# SCH__Atlas_2026-06-22.net
KiCad netlist of a schematic drawn in EasyEDA
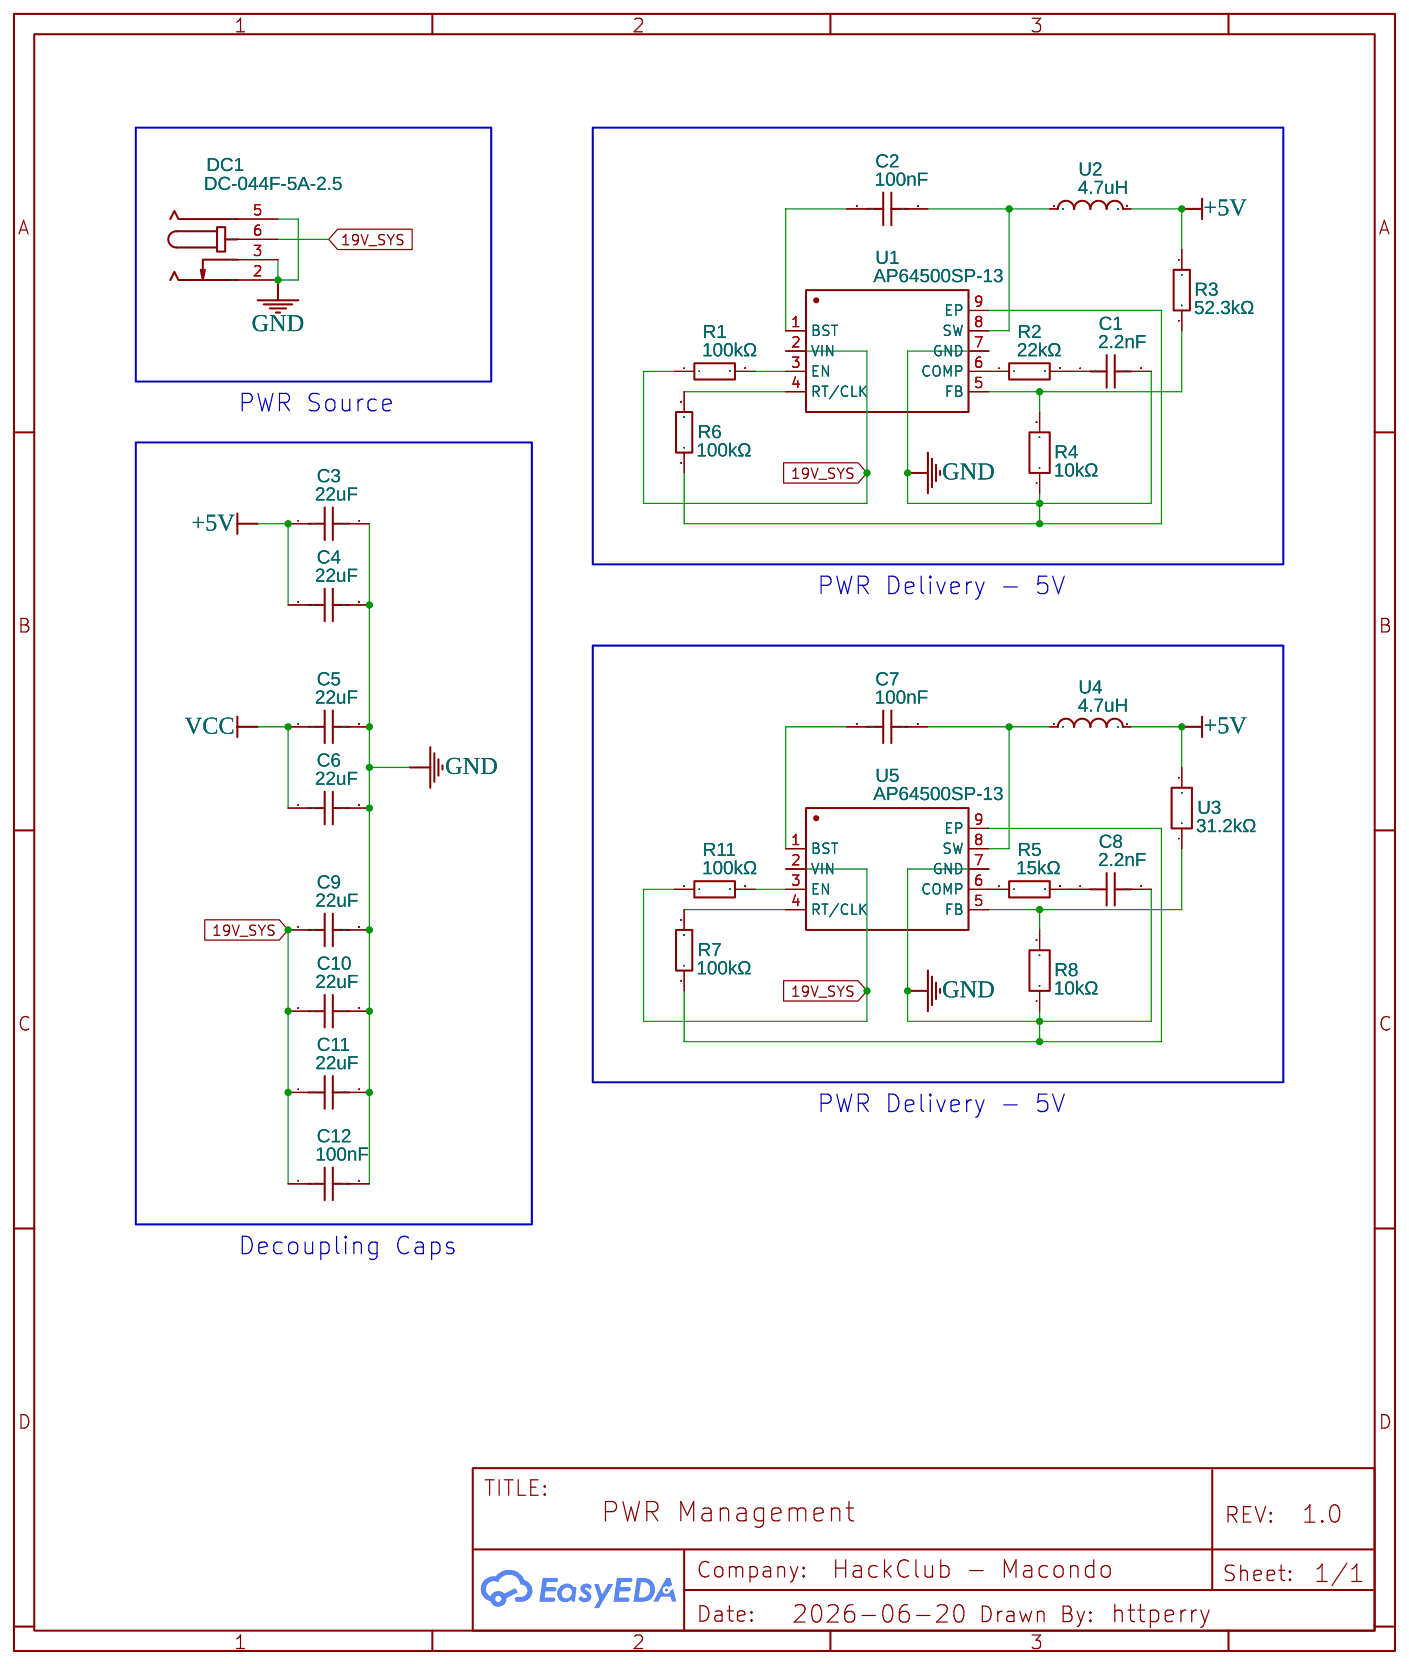
[diagram p0: PWR_Management]
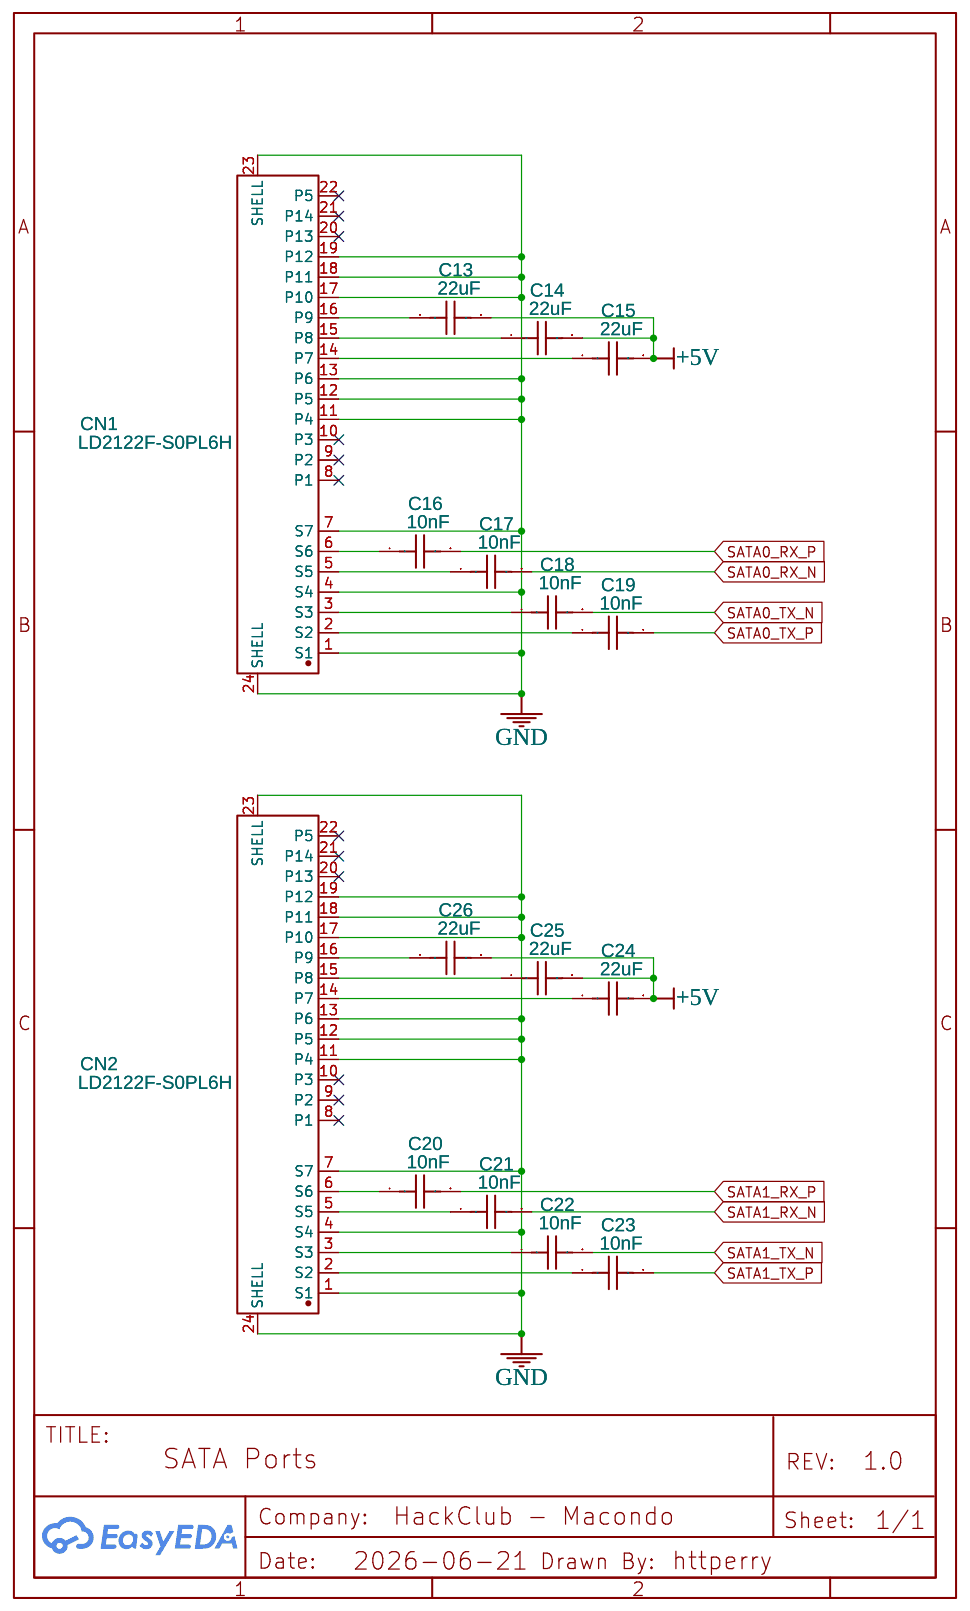
[diagram p1: SATA_Ports]
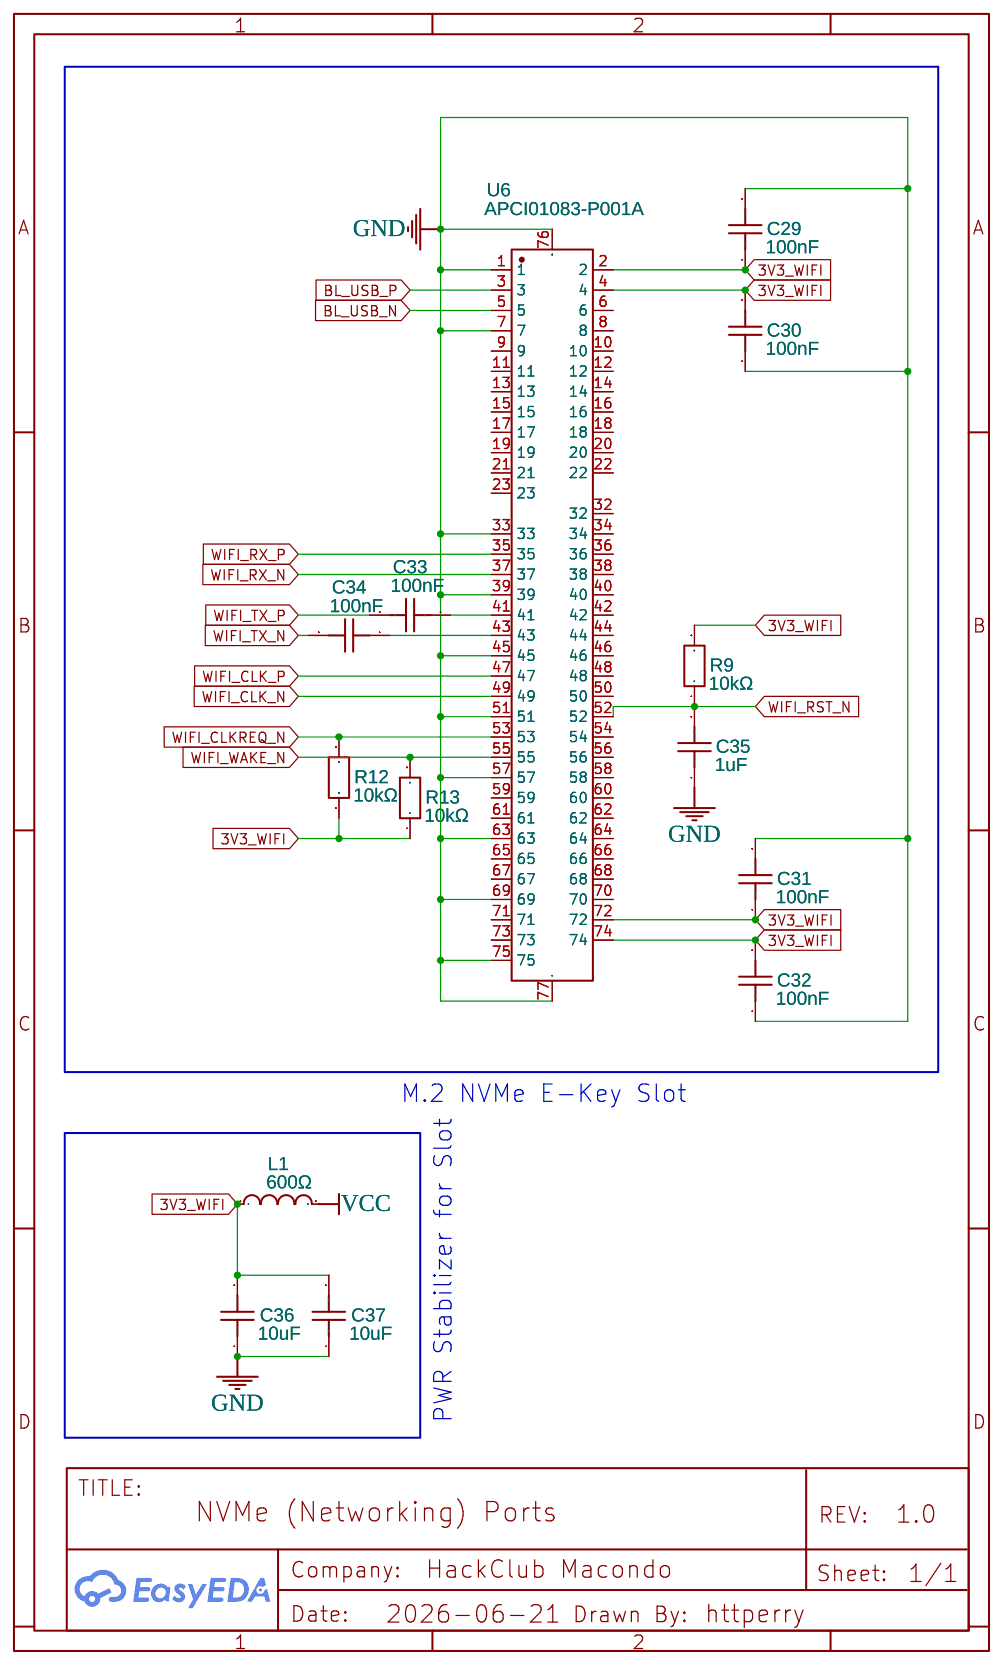
[diagram p2: NVMe_(Networking)_Ports]
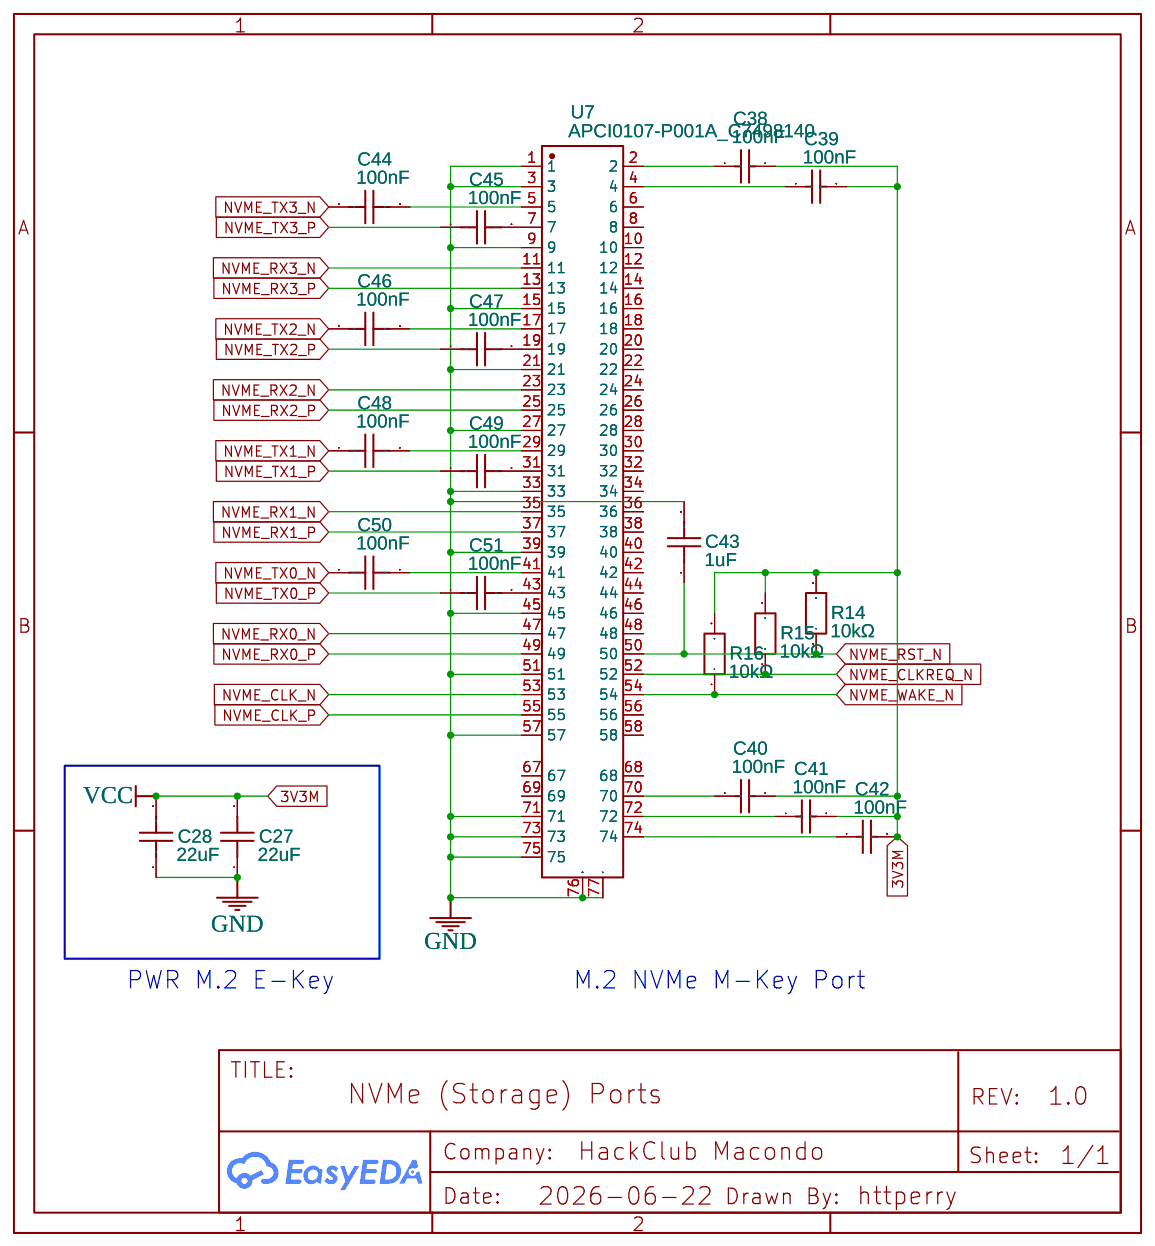
[diagram p3: NVMe_(Storage)_Ports]

(export (version "E")
  (design (tool "Eeschema 10.0.6"))
  (components
    (comp (ref "C1")
      (value "2.2nF")
      (fields
        (field (name "Manufacturer Part") "FCC0603B222K500CT")
        (field (name "Manufacturer") "FOJAN(富捷)")
      )
      (libsource (lib "") (part "FCC0603B222K500CT"))
    )
    (comp (ref "C2")
      (value "100nF")
      (fields
        (field (name "Manufacturer Part") "GRM188R71H104KA93D")
        (field (name "Manufacturer") "muRata(村田)")
      )
      (libsource (lib "") (part "GRM188R71H104KA93D"))
    )
    (comp (ref "C3")
      (value "22uF")
      (fields
        (field (name "Manufacturer Part") "HGC0603R5226M160NTHJ")
        (field (name "Manufacturer") "Chinocera(华瓷)")
      )
      (libsource (lib "") (part "HGC0603R5226M160NTHJ"))
    )
    (comp (ref "C4")
      (value "22uF")
      (fields
        (field (name "Manufacturer Part") "HGC0603R5226M160NTHJ")
        (field (name "Manufacturer") "Chinocera(华瓷)")
      )
      (libsource (lib "") (part "HGC0603R5226M160NTHJ"))
    )
    (comp (ref "C5")
      (value "22uF")
      (fields
        (field (name "Manufacturer Part") "HGC0603R5226M160NTHJ")
        (field (name "Manufacturer") "Chinocera(华瓷)")
      )
      (libsource (lib "") (part "HGC0603R5226M160NTHJ"))
    )
    (comp (ref "C6")
      (value "22uF")
      (fields
        (field (name "Manufacturer Part") "HGC0603R5226M160NTHJ")
        (field (name "Manufacturer") "Chinocera(华瓷)")
      )
      (libsource (lib "") (part "HGC0603R5226M160NTHJ"))
    )
    (comp (ref "C7")
      (value "100nF")
      (fields
        (field (name "Manufacturer Part") "GRM188R71H104KA93D")
        (field (name "Manufacturer") "muRata(村田)")
      )
      (libsource (lib "") (part "GRM188R71H104KA93D"))
    )
    (comp (ref "C8")
      (value "2.2nF")
      (fields
        (field (name "Manufacturer Part") "FCC0603B222K500CT")
        (field (name "Manufacturer") "FOJAN(富捷)")
      )
      (libsource (lib "") (part "FCC0603B222K500CT"))
    )
    (comp (ref "C9")
      (value "22uF")
      (fields
        (field (name "Manufacturer Part") "KCM55QR71H226KH13K")
        (field (name "Manufacturer") "muRata(村田)")
      )
      (libsource (lib "") (part "KCM55QR71H226KH13K"))
    )
    (comp (ref "C10")
      (value "22uF")
      (fields
        (field (name "Manufacturer Part") "KCM55QR71H226KH13K")
        (field (name "Manufacturer") "muRata(村田)")
      )
      (libsource (lib "") (part "KCM55QR71H226KH13K"))
    )
    (comp (ref "C11")
      (value "22uF")
      (fields
        (field (name "Manufacturer Part") "KCM55QR71H226KH13K")
        (field (name "Manufacturer") "muRata(村田)")
      )
      (libsource (lib "") (part "KCM55QR71H226KH13K"))
    )
    (comp (ref "C12")
      (value "100nF")
      (fields
        (field (name "Manufacturer Part") "GRM188R71H104KA93D")
        (field (name "Manufacturer") "muRata(村田)")
      )
      (libsource (lib "") (part "GRM188R71H104KA93D"))
    )
    (comp (ref "DC1")
      (value "DC-044F-5A-2.5")
      (fields (field (name "Manufacturer") "XKB Connection(中国星坤)"))
      (libsource (lib "") (part "DC-044F-5A-2.5"))
    )
    (comp (ref "R1")
      (value "100kΩ")
      (fields (field (name "Manufacturer Part") "RS-03K1003FT") (field (name "Manufacturer") "FH(风华)"))
      (libsource (lib "") (part "RS-03K1003FT_C115320"))
    )
    (comp (ref "R2")
      (value "22kΩ")
      (fields (field (name "Manufacturer Part") "RS-03K2202FT") (field (name "Manufacturer") "FH(风华)"))
      (libsource (lib "") (part "RS-03K2202FT"))
    )
    (comp (ref "R3")
      (value "52.3kΩ")
      (fields (field (name "Manufacturer Part") "RS-03K5232FT") (field (name "Manufacturer") "FH(风华)"))
      (libsource (lib "") (part "RS-03K5232FT"))
    )
    (comp (ref "R4")
      (value "10kΩ")
      (fields (field (name "Manufacturer Part") "AR03BTS1002") (field (name "Manufacturer") "Viking(光颉)"))
      (libsource (lib "") (part "AR03BTS1002"))
    )
    (comp (ref "R5")
      (value "15kΩ")
      (fields (field (name "Manufacturer Part") "CR0603FA1502G") (field (name "Manufacturer") "LIZ(丽智电子)"))
      (libsource (lib "") (part "CR0603FA1502G"))
    )
    (comp (ref "R6")
      (value "100kΩ")
      (fields (field (name "Manufacturer Part") "RS-03K1003FT") (field (name "Manufacturer") "FH(风华)"))
      (libsource (lib "") (part "RS-03K1003FT_C115320_1"))
    )
    (comp (ref "R7")
      (value "100kΩ")
      (fields (field (name "Manufacturer Part") "RS-03K1003FT") (field (name "Manufacturer") "FH(风华)"))
      (libsource (lib "") (part "RS-03K1003FT_C115320_1"))
    )
    (comp (ref "R8")
      (value "10kΩ")
      (fields (field (name "Manufacturer Part") "AR03BTS1002") (field (name "Manufacturer") "Viking(光颉)"))
      (libsource (lib "") (part "AR03BTS1002"))
    )
    (comp (ref "R11")
      (value "100kΩ")
      (fields (field (name "Manufacturer Part") "RS-03K1003FT") (field (name "Manufacturer") "FH(风华)"))
      (libsource (lib "") (part "RS-03K1003FT_C115320"))
    )
    (comp (ref "U1")
      (value "AP64500SP-13")
      (fields (field (name "Manufacturer") "DIODES(美台)"))
      (libsource (lib "") (part "AP64500SP-13"))
    )
    (comp (ref "U2")
      (value "4.7uH")
      (fields (field (name "Manufacturer Part") "APH0630T4R7M") (field (name "Manufacturer") "APV(爱普微)"))
      (libsource (lib "") (part "APH0630T4R7M"))
    )
    (comp (ref "U3")
      (value "31.2kΩ")
      (fields (field (name "Manufacturer Part") "RT0603DRE0731K2L") (field (name "Manufacturer") "YAGEO(国巨)"))
      (libsource (lib "") (part "RT0603DRE0731K2L"))
    )
    (comp (ref "U4")
      (value "4.7uH")
      (fields (field (name "Manufacturer Part") "APH0630T4R7M") (field (name "Manufacturer") "APV(爱普微)"))
      (libsource (lib "") (part "APH0630T4R7M"))
    )
    (comp (ref "U5")
      (value "AP64500SP-13")
      (fields (field (name "Manufacturer") "DIODES(美台)"))
      (libsource (lib "") (part "AP64500SP-13"))
    )
    (comp (ref "C13")
      (value "22uF")
      (fields
        (field (name "Manufacturer Part") "HGC0603R5226M160NTHJ")
        (field (name "Manufacturer") "Chinocera(华瓷)")
      )
      (libsource (lib "") (part "HGC0603R5226M160NTHJ"))
    )
    (comp (ref "C14")
      (value "22uF")
      (fields
        (field (name "Manufacturer Part") "HGC0603R5226M160NTHJ")
        (field (name "Manufacturer") "Chinocera(华瓷)")
      )
      (libsource (lib "") (part "HGC0603R5226M160NTHJ"))
    )
    (comp (ref "C15")
      (value "22uF")
      (fields
        (field (name "Manufacturer Part") "HGC0603R5226M160NTHJ")
        (field (name "Manufacturer") "Chinocera(华瓷)")
      )
      (libsource (lib "") (part "HGC0603R5226M160NTHJ"))
    )
    (comp (ref "C16")
      (value "10nF")
      (fields
        (field (name "Manufacturer Part") "FCC0402B103K500AT")
        (field (name "Manufacturer") "FOJAN(富捷)")
      )
      (libsource (lib "") (part "FCC0402B103K500AT"))
    )
    (comp (ref "C17")
      (value "10nF")
      (fields
        (field (name "Manufacturer Part") "FCC0402B103K500AT")
        (field (name "Manufacturer") "FOJAN(富捷)")
      )
      (libsource (lib "") (part "FCC0402B103K500AT"))
    )
    (comp (ref "C18")
      (value "10nF")
      (fields
        (field (name "Manufacturer Part") "FCC0402B103K500AT")
        (field (name "Manufacturer") "FOJAN(富捷)")
      )
      (libsource (lib "") (part "FCC0402B103K500AT"))
    )
    (comp (ref "C19")
      (value "10nF")
      (fields
        (field (name "Manufacturer Part") "FCC0402B103K500AT")
        (field (name "Manufacturer") "FOJAN(富捷)")
      )
      (libsource (lib "") (part "FCC0402B103K500AT"))
    )
    (comp (ref "C20")
      (value "10nF")
      (fields
        (field (name "Manufacturer Part") "FCC0402B103K500AT")
        (field (name "Manufacturer") "FOJAN(富捷)")
      )
      (libsource (lib "") (part "FCC0402B103K500AT"))
    )
    (comp (ref "C21")
      (value "10nF")
      (fields
        (field (name "Manufacturer Part") "FCC0402B103K500AT")
        (field (name "Manufacturer") "FOJAN(富捷)")
      )
      (libsource (lib "") (part "FCC0402B103K500AT"))
    )
    (comp (ref "C22")
      (value "10nF")
      (fields
        (field (name "Manufacturer Part") "FCC0402B103K500AT")
        (field (name "Manufacturer") "FOJAN(富捷)")
      )
      (libsource (lib "") (part "FCC0402B103K500AT"))
    )
    (comp (ref "C23")
      (value "10nF")
      (fields
        (field (name "Manufacturer Part") "FCC0402B103K500AT")
        (field (name "Manufacturer") "FOJAN(富捷)")
      )
      (libsource (lib "") (part "FCC0402B103K500AT"))
    )
    (comp (ref "C24")
      (value "22uF")
      (fields
        (field (name "Manufacturer Part") "HGC0603R5226M160NTHJ")
        (field (name "Manufacturer") "Chinocera(华瓷)")
      )
      (libsource (lib "") (part "HGC0603R5226M160NTHJ"))
    )
    (comp (ref "C25")
      (value "22uF")
      (fields
        (field (name "Manufacturer Part") "HGC0603R5226M160NTHJ")
        (field (name "Manufacturer") "Chinocera(华瓷)")
      )
      (libsource (lib "") (part "HGC0603R5226M160NTHJ"))
    )
    (comp (ref "C26")
      (value "22uF")
      (fields
        (field (name "Manufacturer Part") "HGC0603R5226M160NTHJ")
        (field (name "Manufacturer") "Chinocera(华瓷)")
      )
      (libsource (lib "") (part "HGC0603R5226M160NTHJ"))
    )
    (comp (ref "CN1")
      (value "LD2122F-S0PL6H")
      (fields (field (name "Manufacturer") "FOXCONN(富士康)"))
      (libsource (lib "") (part "LD2122F-S0PL6H"))
    )
    (comp (ref "CN2")
      (value "LD2122F-S0PL6H")
      (fields (field (name "Manufacturer") "FOXCONN(富士康)"))
      (libsource (lib "") (part "LD2122F-S0PL6H"))
    )
    (comp (ref "C29")
      (value "100nF")
      (fields
        (field (name "Manufacturer Part") "CC0402KRX5R6BB104")
        (field (name "Manufacturer") "YAGEO(国巨)")
      )
      (libsource (lib "") (part "CC0402KRX5R6BB104"))
    )
    (comp (ref "C30")
      (value "100nF")
      (fields
        (field (name "Manufacturer Part") "CC0402KRX5R6BB104")
        (field (name "Manufacturer") "YAGEO(国巨)")
      )
      (libsource (lib "") (part "CC0402KRX5R6BB104"))
    )
    (comp (ref "C31")
      (value "100nF")
      (fields
        (field (name "Manufacturer Part") "CC0402KRX5R6BB104")
        (field (name "Manufacturer") "YAGEO(国巨)")
      )
      (libsource (lib "") (part "CC0402KRX5R6BB104"))
    )
    (comp (ref "C32")
      (value "100nF")
      (fields
        (field (name "Manufacturer Part") "CC0402KRX5R6BB104")
        (field (name "Manufacturer") "YAGEO(国巨)")
      )
      (libsource (lib "") (part "CC0402KRX5R6BB104"))
    )
    (comp (ref "C33")
      (value "100nF")
      (fields
        (field (name "Manufacturer Part") "CC0402KRX5R6BB104")
        (field (name "Manufacturer") "YAGEO(国巨)")
      )
      (libsource (lib "") (part "CC0402KRX5R6BB104_1"))
    )
    (comp (ref "C34")
      (value "100nF")
      (fields
        (field (name "Manufacturer Part") "CC0402KRX5R6BB104")
        (field (name "Manufacturer") "YAGEO(国巨)")
      )
      (libsource (lib "") (part "CC0402KRX5R6BB104_1"))
    )
    (comp (ref "C35")
      (value "1uF")
      (fields
        (field (name "Manufacturer Part") "TCC0402X5R105K160AT")
        (field (name "Manufacturer") "CCTC(三环)")
      )
      (libsource (lib "") (part "TCC0402X5R105K160AT"))
    )
    (comp (ref "C36")
      (value "10uF")
      (fields
        (field (name "Manufacturer Part") "CGA0805X5R106K500MT")
        (field (name "Manufacturer") "HRE(芯声)")
      )
      (libsource (lib "") (part "CGA0805X5R106K500MT"))
    )
    (comp (ref "C37")
      (value "10uF")
      (fields
        (field (name "Manufacturer Part") "CGA0805X5R106K500MT")
        (field (name "Manufacturer") "HRE(芯声)")
      )
      (libsource (lib "") (part "CGA0805X5R106K500MT"))
    )
    (comp (ref "L1")
      (value "600Ω")
      (fields (field (name "Manufacturer Part") "MPZ2012S601AT000") (field (name "Manufacturer") "TDK"))
      (libsource (lib "") (part "MPZ2012S601AT000"))
    )
    (comp (ref "R9")
      (value "10kΩ")
      (fields (field (name "Manufacturer Part") "FRC0402F1002TS") (field (name "Manufacturer") "FOJAN(富捷)"))
      (libsource (lib "") (part "FRC0402F1002TS"))
    )
    (comp (ref "R12")
      (value "10kΩ")
      (fields (field (name "Manufacturer Part") "FRC0402F1002TS") (field (name "Manufacturer") "FOJAN(富捷)"))
      (libsource (lib "") (part "FRC0402F1002TS"))
    )
    (comp (ref "R13")
      (value "10kΩ")
      (fields (field (name "Manufacturer Part") "FRC0402F1002TS") (field (name "Manufacturer") "FOJAN(富捷)"))
      (libsource (lib "") (part "FRC0402F1002TS"))
    )
    (comp (ref "U6")
      (value "APCI01083-P001A")
      (fields (field (name "Manufacturer") "LX(连欣科技)"))
      (libsource (lib "") (part "APCI01083-P001A"))
    )
    (comp (ref "C27")
      (value "22uF")
      (fields
        (field (name "Manufacturer Part") "CL21A226MAYNNNE")
        (field (name "Manufacturer") "SAMSUNG(三星)")
      )
      (libsource (lib "") (part "CL21A226MAYNNNE"))
    )
    (comp (ref "C28")
      (value "22uF")
      (fields
        (field (name "Manufacturer Part") "CL21A226MAYNNNE")
        (field (name "Manufacturer") "SAMSUNG(三星)")
      )
      (libsource (lib "") (part "CL21A226MAYNNNE"))
    )
    (comp (ref "C38")
      (value "100nF")
      (fields
        (field (name "Manufacturer Part") "CC0402KRX5R8BB104")
        (field (name "Manufacturer") "YAGEO(国巨)")
      )
      (libsource (lib "") (part "CC0402KRX5R8BB104"))
    )
    (comp (ref "C39")
      (value "100nF")
      (fields
        (field (name "Manufacturer Part") "CC0402KRX5R8BB104")
        (field (name "Manufacturer") "YAGEO(国巨)")
      )
      (libsource (lib "") (part "CC0402KRX5R8BB104"))
    )
    (comp (ref "C40")
      (value "100nF")
      (fields
        (field (name "Manufacturer Part") "CC0402KRX5R8BB104")
        (field (name "Manufacturer") "YAGEO(国巨)")
      )
      (libsource (lib "") (part "CC0402KRX5R8BB104"))
    )
    (comp (ref "C41")
      (value "100nF")
      (fields
        (field (name "Manufacturer Part") "CC0402KRX5R8BB104")
        (field (name "Manufacturer") "YAGEO(国巨)")
      )
      (libsource (lib "") (part "CC0402KRX5R8BB104"))
    )
    (comp (ref "C42")
      (value "100nF")
      (fields
        (field (name "Manufacturer Part") "CC0402KRX5R8BB104")
        (field (name "Manufacturer") "YAGEO(国巨)")
      )
      (libsource (lib "") (part "CC0402KRX5R8BB104"))
    )
    (comp (ref "C43")
      (value "1uF")
      (fields
        (field (name "Manufacturer Part") "HGC0402R5105K500NTEJ")
        (field (name "Manufacturer") "Chinocera(华瓷)")
      )
      (libsource (lib "") (part "HGC0402R5105K500NTEJ"))
    )
    (comp (ref "C44")
      (value "100nF")
      (fields
        (field (name "Manufacturer Part") "GRM155R71H104KE14J")
        (field (name "Manufacturer") "muRata(村田)")
      )
      (libsource (lib "") (part "GRM155R71H104KE14J"))
    )
    (comp (ref "C45")
      (value "100nF")
      (fields
        (field (name "Manufacturer Part") "GRM155R71H104KE14J")
        (field (name "Manufacturer") "muRata(村田)")
      )
      (libsource (lib "") (part "GRM155R71H104KE14J"))
    )
    (comp (ref "C46")
      (value "100nF")
      (fields
        (field (name "Manufacturer Part") "GRM155R71H104KE14J")
        (field (name "Manufacturer") "muRata(村田)")
      )
      (libsource (lib "") (part "GRM155R71H104KE14J"))
    )
    (comp (ref "C47")
      (value "100nF")
      (fields
        (field (name "Manufacturer Part") "GRM155R71H104KE14J")
        (field (name "Manufacturer") "muRata(村田)")
      )
      (libsource (lib "") (part "GRM155R71H104KE14J"))
    )
    (comp (ref "C48")
      (value "100nF")
      (fields
        (field (name "Manufacturer Part") "GRM155R71H104KE14J")
        (field (name "Manufacturer") "muRata(村田)")
      )
      (libsource (lib "") (part "GRM155R71H104KE14J"))
    )
    (comp (ref "C49")
      (value "100nF")
      (fields
        (field (name "Manufacturer Part") "GRM155R71H104KE14J")
        (field (name "Manufacturer") "muRata(村田)")
      )
      (libsource (lib "") (part "GRM155R71H104KE14J"))
    )
    (comp (ref "C50")
      (value "100nF")
      (fields
        (field (name "Manufacturer Part") "GRM155R71H104KE14J")
        (field (name "Manufacturer") "muRata(村田)")
      )
      (libsource (lib "") (part "GRM155R71H104KE14J"))
    )
    (comp (ref "C51")
      (value "100nF")
      (fields
        (field (name "Manufacturer Part") "GRM155R71H104KE14J")
        (field (name "Manufacturer") "muRata(村田)")
      )
      (libsource (lib "") (part "GRM155R71H104KE14J"))
    )
    (comp (ref "R14")
      (value "10kΩ")
      (fields (field (name "Manufacturer Part") "FRC0402F1002TS") (field (name "Manufacturer") "FOJAN(富捷)"))
      (libsource (lib "") (part "FRC0402F1002TS"))
    )
    (comp (ref "R15")
      (value "10kΩ")
      (fields (field (name "Manufacturer Part") "FRC0402F1002TS") (field (name "Manufacturer") "FOJAN(富捷)"))
      (libsource (lib "") (part "FRC0402F1002TS"))
    )
    (comp (ref "R16")
      (value "10kΩ")
      (fields (field (name "Manufacturer Part") "FRC0402F1002TS") (field (name "Manufacturer") "FOJAN(富捷)"))
      (libsource (lib "") (part "FRC0402F1002TS"))
    )
    (comp (ref "U7")
      (value "APCI0107-P001A_C7498140")
      (fields (field (name "Manufacturer Part") "APCI0107-P001A") (field (name "Manufacturer") "LX(连欣科技)"))
      (libsource (lib "") (part "APCI0107-P001A_C7498140"))
    )
  )
  (nets
    (net (code "1") (name "+5V") (class "Default")
      (node (ref "C13") (pin "2") (pinfunction "2_2") (pintype "unspecified"))
      (node (ref "C14") (pin "2") (pinfunction "2_2") (pintype "unspecified"))
      (node (ref "C15") (pin "2") (pinfunction "2_2") (pintype "unspecified"))
      (node (ref "C24") (pin "2") (pinfunction "2_2") (pintype "unspecified"))
      (node (ref "C25") (pin "2") (pinfunction "2_2") (pintype "unspecified"))
      (node (ref "C26") (pin "2") (pinfunction "2_2") (pintype "unspecified"))
      (node (ref "C3") (pin "1") (pinfunction "1_1") (pintype "unspecified"))
      (node (ref "C4") (pin "1") (pinfunction "1_1") (pintype "unspecified"))
      (node (ref "R3") (pin "1") (pinfunction "1_1") (pintype "unspecified"))
      (node (ref "U2") (pin "2") (pinfunction "2_2") (pintype "unspecified"))
      (node (ref "U3") (pin "2") (pinfunction "2_2") (pintype "unspecified"))
      (node (ref "U4") (pin "2") (pinfunction "2_2") (pintype "unspecified"))
    )
    (net (code "2") (name "3V3M") (class "Default")
      (node (ref "C27") (pin "2") (pinfunction "2_2") (pintype "unspecified"))
      (node (ref "C28") (pin "2") (pinfunction "2_2") (pintype "unspecified"))
      (node (ref "C38") (pin "2") (pinfunction "2_2") (pintype "input"))
      (node (ref "C39") (pin "2") (pinfunction "2_2") (pintype "input"))
      (node (ref "C40") (pin "2") (pinfunction "2_2") (pintype "input"))
      (node (ref "C41") (pin "2") (pinfunction "2_2") (pintype "input"))
      (node (ref "C42") (pin "2") (pinfunction "2_2") (pintype "input"))
      (node (ref "C5") (pin "1") (pinfunction "1_1") (pintype "unspecified"))
      (node (ref "C6") (pin "1") (pinfunction "1_1") (pintype "unspecified"))
      (node (ref "L1") (pin "2") (pinfunction "2_2") (pintype "unspecified"))
      (node (ref "R14") (pin "2") (pinfunction "2_2") (pintype "unspecified"))
      (node (ref "R15") (pin "2") (pinfunction "2_2") (pintype "unspecified"))
      (node (ref "R16") (pin "2") (pinfunction "2_2") (pintype "unspecified"))
    )
    (net (code "3") (name "3V3_WIFI") (class "Default")
      (node (ref "C29") (pin "1") (pinfunction "1_1") (pintype "unspecified"))
      (node (ref "C30") (pin "2") (pinfunction "2_2") (pintype "unspecified"))
      (node (ref "C31") (pin "1") (pinfunction "1_1") (pintype "unspecified"))
      (node (ref "C32") (pin "2") (pinfunction "2_2") (pintype "unspecified"))
      (node (ref "C36") (pin "2") (pinfunction "2_2") (pintype "unspecified"))
      (node (ref "C37") (pin "2") (pinfunction "2_2") (pintype "unspecified"))
      (node (ref "L1") (pin "1") (pinfunction "1_1") (pintype "unspecified"))
      (node (ref "R12") (pin "1") (pinfunction "1_1") (pintype "unspecified"))
      (node (ref "R13") (pin "1") (pinfunction "1_1") (pintype "unspecified"))
      (node (ref "R9") (pin "2") (pinfunction "2_2") (pintype "unspecified"))
      (node (ref "U6") (pin "2") (pinfunction "2_2") (pintype "unspecified"))
      (node (ref "U6") (pin "4") (pinfunction "4_4") (pintype "unspecified"))
      (node (ref "U6") (pin "72") (pinfunction "72_72") (pintype "unspecified"))
      (node (ref "U6") (pin "74") (pinfunction "74_74") (pintype "unspecified"))
    )
    (net (code "4") (name "19V_SYS") (class "Default")
      (node (ref "C10") (pin "1") (pinfunction "1_1") (pintype "unspecified"))
      (node (ref "C11") (pin "1") (pinfunction "1_1") (pintype "unspecified"))
      (node (ref "C12") (pin "1") (pinfunction "1_1") (pintype "unspecified"))
      (node (ref "C9") (pin "1") (pinfunction "1_1") (pintype "unspecified"))
      (node (ref "DC1") (pin "6") (pinfunction "6_6") (pintype "unspecified"))
      (node (ref "R1") (pin "1") (pinfunction "1_1") (pintype "unspecified"))
      (node (ref "R11") (pin "1") (pinfunction "1_1") (pintype "unspecified"))
      (node (ref "U1") (pin "2") (pinfunction "VIN_2") (pintype "unspecified"))
      (node (ref "U5") (pin "2") (pinfunction "VIN_2") (pintype "unspecified"))
    )
    (net (code "5") (name "BL_USB_N") (class "Default")
      (node (ref "U6") (pin "5") (pinfunction "5_5") (pintype "unspecified"))
    )
    (net (code "6") (name "BL_USB_P") (class "Default")
      (node (ref "U6") (pin "3") (pinfunction "3_3") (pintype "unspecified"))
    )
    (net (code "7") (name "GND") (class "Default")
      (node (ref "C1") (pin "2") (pinfunction "2_2") (pintype "unspecified"))
      (node (ref "C10") (pin "2") (pinfunction "2_2") (pintype "unspecified"))
      (node (ref "C11") (pin "2") (pinfunction "2_2") (pintype "unspecified"))
      (node (ref "C12") (pin "2") (pinfunction "2_2") (pintype "unspecified"))
      (node (ref "C27") (pin "1") (pinfunction "1_1") (pintype "unspecified"))
      (node (ref "C28") (pin "1") (pinfunction "1_1") (pintype "unspecified"))
      (node (ref "C29") (pin "2") (pinfunction "2_2") (pintype "unspecified"))
      (node (ref "C3") (pin "2") (pinfunction "2_2") (pintype "unspecified"))
      (node (ref "C30") (pin "1") (pinfunction "1_1") (pintype "unspecified"))
      (node (ref "C31") (pin "2") (pinfunction "2_2") (pintype "unspecified"))
      (node (ref "C32") (pin "1") (pinfunction "1_1") (pintype "unspecified"))
      (node (ref "C35") (pin "1") (pinfunction "1_1") (pintype "unspecified"))
      (node (ref "C36") (pin "1") (pinfunction "1_1") (pintype "unspecified"))
      (node (ref "C37") (pin "1") (pinfunction "1_1") (pintype "unspecified"))
      (node (ref "C4") (pin "2") (pinfunction "2_2") (pintype "unspecified"))
      (node (ref "C43") (pin "2") (pinfunction "2_2") (pintype "unspecified"))
      (node (ref "C5") (pin "2") (pinfunction "2_2") (pintype "unspecified"))
      (node (ref "C6") (pin "2") (pinfunction "2_2") (pintype "unspecified"))
      (node (ref "C8") (pin "2") (pinfunction "2_2") (pintype "unspecified"))
      (node (ref "C9") (pin "2") (pinfunction "2_2") (pintype "unspecified"))
      (node (ref "CN1") (pin "1") (pinfunction "S1_1") (pintype "unspecified"))
      (node (ref "CN1") (pin "11") (pinfunction "P4_11") (pintype "unspecified"))
      (node (ref "CN1") (pin "12") (pinfunction "P5_12") (pintype "unspecified"))
      (node (ref "CN1") (pin "13") (pinfunction "P6_13") (pintype "unspecified"))
      (node (ref "CN1") (pin "17") (pinfunction "P10_17") (pintype "unspecified"))
      (node (ref "CN1") (pin "18") (pinfunction "P11_18") (pintype "unspecified"))
      (node (ref "CN1") (pin "19") (pinfunction "P12_19") (pintype "unspecified"))
      (node (ref "CN1") (pin "23") (pinfunction "SHELL_23") (pintype "unspecified"))
      (node (ref "CN1") (pin "24") (pinfunction "SHELL_24") (pintype "unspecified"))
      (node (ref "CN1") (pin "4") (pinfunction "S4_4") (pintype "unspecified"))
      (node (ref "CN1") (pin "7") (pinfunction "S7_7") (pintype "unspecified"))
      (node (ref "CN2") (pin "1") (pinfunction "S1_1") (pintype "unspecified"))
      (node (ref "CN2") (pin "11") (pinfunction "P4_11") (pintype "unspecified"))
      (node (ref "CN2") (pin "12") (pinfunction "P5_12") (pintype "unspecified"))
      (node (ref "CN2") (pin "13") (pinfunction "P6_13") (pintype "unspecified"))
      (node (ref "CN2") (pin "17") (pinfunction "P10_17") (pintype "unspecified"))
      (node (ref "CN2") (pin "18") (pinfunction "P11_18") (pintype "unspecified"))
      (node (ref "CN2") (pin "19") (pinfunction "P12_19") (pintype "unspecified"))
      (node (ref "CN2") (pin "23") (pinfunction "SHELL_23") (pintype "unspecified"))
      (node (ref "CN2") (pin "24") (pinfunction "SHELL_24") (pintype "unspecified"))
      (node (ref "CN2") (pin "4") (pinfunction "S4_4") (pintype "unspecified"))
      (node (ref "CN2") (pin "7") (pinfunction "S7_7") (pintype "unspecified"))
      (node (ref "DC1") (pin "2") (pinfunction "2_2") (pintype "unspecified"))
      (node (ref "DC1") (pin "3") (pinfunction "3_3") (pintype "unspecified"))
      (node (ref "DC1") (pin "5") (pinfunction "5_5") (pintype "unspecified"))
      (node (ref "R4") (pin "1") (pinfunction "1_1") (pintype "unspecified"))
      (node (ref "R6") (pin "1") (pinfunction "1_1") (pintype "unspecified"))
      (node (ref "R7") (pin "1") (pinfunction "1_1") (pintype "unspecified"))
      (node (ref "R8") (pin "1") (pinfunction "1_1") (pintype "unspecified"))
      (node (ref "U1") (pin "7") (pinfunction "GND_7") (pintype "unspecified"))
      (node (ref "U1") (pin "9") (pinfunction "EP_9") (pintype "unspecified"))
      (node (ref "U5") (pin "7") (pinfunction "GND_7") (pintype "unspecified"))
      (node (ref "U5") (pin "9") (pinfunction "EP_9") (pintype "unspecified"))
      (node (ref "U6") (pin "1") (pinfunction "1_1") (pintype "unspecified"))
      (node (ref "U6") (pin "33") (pinfunction "33_33") (pintype "unspecified"))
      (node (ref "U6") (pin "39") (pinfunction "39_39") (pintype "unspecified"))
      (node (ref "U6") (pin "45") (pinfunction "45_45") (pintype "unspecified"))
      (node (ref "U6") (pin "51") (pinfunction "51_51") (pintype "unspecified"))
      (node (ref "U6") (pin "57") (pinfunction "57_57") (pintype "unspecified"))
      (node (ref "U6") (pin "63") (pinfunction "63_63") (pintype "unspecified"))
      (node (ref "U6") (pin "69") (pinfunction "69_69") (pintype "unspecified"))
      (node (ref "U6") (pin "7") (pinfunction "7_7") (pintype "unspecified"))
      (node (ref "U6") (pin "75") (pinfunction "75_75") (pintype "unspecified"))
      (node (ref "U6") (pin "76") (pinfunction "76_76") (pintype "unspecified"))
      (node (ref "U6") (pin "77") (pinfunction "77_77") (pintype "unspecified"))
      (node (ref "U7") (pin "1") (pinfunction "1_1") (pintype "unspecified"))
      (node (ref "U7") (pin "15") (pinfunction "15_15") (pintype "unspecified"))
      (node (ref "U7") (pin "21") (pinfunction "21_21") (pintype "unspecified"))
      (node (ref "U7") (pin "27") (pinfunction "27_27") (pintype "unspecified"))
      (node (ref "U7") (pin "3") (pinfunction "3_3") (pintype "unspecified"))
      (node (ref "U7") (pin "33") (pinfunction "33_33") (pintype "unspecified"))
      (node (ref "U7") (pin "39") (pinfunction "39_39") (pintype "unspecified"))
      (node (ref "U7") (pin "45") (pinfunction "45_45") (pintype "unspecified"))
      (node (ref "U7") (pin "51") (pinfunction "51_51") (pintype "unspecified"))
      (node (ref "U7") (pin "57") (pinfunction "57_57") (pintype "unspecified"))
      (node (ref "U7") (pin "71") (pinfunction "71_71") (pintype "unspecified"))
      (node (ref "U7") (pin "73") (pinfunction "73_73") (pintype "unspecified"))
      (node (ref "U7") (pin "75") (pinfunction "75_75") (pintype "unspecified"))
      (node (ref "U7") (pin "76") (pinfunction "76_76") (pintype "unspecified"))
      (node (ref "U7") (pin "77") (pinfunction "77_77") (pintype "unspecified"))
      (node (ref "U7") (pin "9") (pinfunction "9_9") (pintype "unspecified"))
    )
    (net (code "8") (name "NVME_CLKREQ_N") (class "Default")
      (node (ref "R15") (pin "1") (pinfunction "1_1") (pintype "unspecified"))
      (node (ref "U7") (pin "52") (pinfunction "52_52") (pintype "unspecified"))
    )
    (net (code "9") (name "NVME_CLK_N") (class "Default")
      (node (ref "U7") (pin "53") (pinfunction "53_53") (pintype "unspecified"))
    )
    (net (code "10") (name "NVME_CLK_P") (class "Default")
      (node (ref "U7") (pin "55") (pinfunction "55_55") (pintype "unspecified"))
    )
    (net (code "11") (name "NVME_RST_N") (class "Default")
      (node (ref "C43") (pin "1") (pinfunction "1_1") (pintype "unspecified"))
      (node (ref "R14") (pin "1") (pinfunction "1_1") (pintype "unspecified"))
      (node (ref "U7") (pin "50") (pinfunction "50_50") (pintype "unspecified"))
    )
    (net (code "12") (name "NVME_RX0_N") (class "Default")
      (node (ref "U7") (pin "47") (pinfunction "47_47") (pintype "unspecified"))
    )
    (net (code "13") (name "NVME_RX0_P") (class "Default")
      (node (ref "U7") (pin "49") (pinfunction "49_49") (pintype "unspecified"))
    )
    (net (code "14") (name "NVME_RX1_N") (class "Default")
      (node (ref "U7") (pin "35") (pinfunction "35_35") (pintype "unspecified"))
    )
    (net (code "15") (name "NVME_RX1_P") (class "Default")
      (node (ref "U7") (pin "37") (pinfunction "37_37") (pintype "unspecified"))
    )
    (net (code "16") (name "NVME_RX2_N") (class "Default")
      (node (ref "U7") (pin "23") (pinfunction "23_23") (pintype "unspecified"))
    )
    (net (code "17") (name "NVME_RX2_P") (class "Default")
      (node (ref "U7") (pin "25") (pinfunction "25_25") (pintype "unspecified"))
    )
    (net (code "18") (name "NVME_RX3_N") (class "Default")
      (node (ref "U7") (pin "11") (pinfunction "11_11") (pintype "unspecified"))
    )
    (net (code "19") (name "NVME_RX3_P") (class "Default")
      (node (ref "U7") (pin "13") (pinfunction "13_13") (pintype "unspecified"))
    )
    (net (code "20") (name "NVME_TX0_N") (class "Default")
      (node (ref "C50") (pin "1") (pinfunction "1_1") (pintype "unspecified"))
    )
    (net (code "21") (name "NVME_TX0_P") (class "Default")
      (node (ref "C51") (pin "1") (pinfunction "1_1") (pintype "unspecified"))
    )
    (net (code "22") (name "NVME_TX1_N") (class "Default")
      (node (ref "C48") (pin "1") (pinfunction "1_1") (pintype "unspecified"))
    )
    (net (code "23") (name "NVME_TX1_P") (class "Default")
      (node (ref "C49") (pin "1") (pinfunction "1_1") (pintype "unspecified"))
    )
    (net (code "24") (name "NVME_TX2_N") (class "Default")
      (node (ref "C46") (pin "1") (pinfunction "1_1") (pintype "unspecified"))
    )
    (net (code "25") (name "NVME_TX2_P") (class "Default")
      (node (ref "C47") (pin "1") (pinfunction "1_1") (pintype "unspecified"))
    )
    (net (code "26") (name "NVME_TX3_N") (class "Default")
      (node (ref "C44") (pin "1") (pinfunction "1_1") (pintype "unspecified"))
    )
    (net (code "27") (name "NVME_TX3_P") (class "Default")
      (node (ref "C45") (pin "1") (pinfunction "1_1") (pintype "unspecified"))
    )
    (net (code "28") (name "NVME_WAKE_N") (class "Default")
      (node (ref "R16") (pin "1") (pinfunction "1_1") (pintype "unspecified"))
      (node (ref "U7") (pin "54") (pinfunction "54_54") (pintype "unspecified"))
    )
    (net (code "29") (name "Net-(C1-Pad1)") (class "Default")
      (node (ref "C1") (pin "1") (pinfunction "1_1") (pintype "unspecified"))
      (node (ref "R2") (pin "2") (pinfunction "2_2") (pintype "unspecified"))
    )
    (net (code "30") (name "Net-(C8-Pad1)") (class "Default")
      (node (ref "C8") (pin "1") (pinfunction "1_1") (pintype "unspecified"))
      (node (ref "R5") (pin "2") (pinfunction "2_2") (pintype "input"))
    )
    (net (code "31") (name "Net-(C33-Pad1)") (class "Default")
      (node (ref "C33") (pin "1") (pinfunction "1_1") (pintype "unspecified"))
      (node (ref "U6") (pin "41") (pinfunction "41_41") (pintype "unspecified"))
    )
    (net (code "32") (name "Net-(C34-Pad1)") (class "Default")
      (node (ref "C34") (pin "1") (pinfunction "1_1") (pintype "unspecified"))
      (node (ref "U6") (pin "43") (pinfunction "43_43") (pintype "unspecified"))
    )
    (net (code "33") (name "Net-(C38-Pad1)") (class "Default")
      (node (ref "C38") (pin "1") (pinfunction "1_1") (pintype "input"))
      (node (ref "U7") (pin "2") (pinfunction "2_2") (pintype "unspecified"))
    )
    (net (code "34") (name "Net-(C39-Pad1)") (class "Default")
      (node (ref "C39") (pin "1") (pinfunction "1_1") (pintype "input"))
      (node (ref "U7") (pin "4") (pinfunction "4_4") (pintype "unspecified"))
    )
    (net (code "35") (name "Net-(C40-Pad1)") (class "Default")
      (node (ref "C40") (pin "1") (pinfunction "1_1") (pintype "input"))
      (node (ref "U7") (pin "70") (pinfunction "70_70") (pintype "unspecified"))
    )
    (net (code "36") (name "Net-(C41-Pad1)") (class "Default")
      (node (ref "C41") (pin "1") (pinfunction "1_1") (pintype "input"))
      (node (ref "U7") (pin "72") (pinfunction "72_72") (pintype "unspecified"))
    )
    (net (code "37") (name "Net-(C42-Pad1)") (class "Default")
      (node (ref "C42") (pin "1") (pinfunction "1_1") (pintype "input"))
      (node (ref "U7") (pin "74") (pinfunction "74_74") (pintype "unspecified"))
    )
    (net (code "38") (name "Net-(C44-Pad2)") (class "Default")
      (node (ref "C44") (pin "2") (pinfunction "2_2") (pintype "unspecified"))
      (node (ref "U7") (pin "5") (pinfunction "5_5") (pintype "unspecified"))
    )
    (net (code "39") (name "Net-(C45-Pad2)") (class "Default")
      (node (ref "C45") (pin "2") (pinfunction "2_2") (pintype "unspecified"))
      (node (ref "U7") (pin "7") (pinfunction "7_7") (pintype "unspecified"))
    )
    (net (code "40") (name "Net-(C46-Pad2)") (class "Default")
      (node (ref "C46") (pin "2") (pinfunction "2_2") (pintype "unspecified"))
      (node (ref "U7") (pin "17") (pinfunction "17_17") (pintype "unspecified"))
    )
    (net (code "41") (name "Net-(C47-Pad2)") (class "Default")
      (node (ref "C47") (pin "2") (pinfunction "2_2") (pintype "unspecified"))
      (node (ref "U7") (pin "19") (pinfunction "19_19") (pintype "unspecified"))
    )
    (net (code "42") (name "Net-(C48-Pad2)") (class "Default")
      (node (ref "C48") (pin "2") (pinfunction "2_2") (pintype "unspecified"))
      (node (ref "U7") (pin "29") (pinfunction "29_29") (pintype "unspecified"))
    )
    (net (code "43") (name "Net-(C49-Pad2)") (class "Default")
      (node (ref "C49") (pin "2") (pinfunction "2_2") (pintype "unspecified"))
      (node (ref "U7") (pin "31") (pinfunction "31_31") (pintype "unspecified"))
    )
    (net (code "44") (name "Net-(C50-Pad2)") (class "Default")
      (node (ref "C50") (pin "2") (pinfunction "2_2") (pintype "unspecified"))
      (node (ref "U7") (pin "41") (pinfunction "41_41") (pintype "unspecified"))
    )
    (net (code "45") (name "Net-(C51-Pad2)") (class "Default")
      (node (ref "C51") (pin "2") (pinfunction "2_2") (pintype "unspecified"))
      (node (ref "U7") (pin "43") (pinfunction "43_43") (pintype "unspecified"))
    )
    (net (code "46") (name "Net-(CN1-P7)") (class "Default")
      (node (ref "C15") (pin "1") (pinfunction "1_1") (pintype "unspecified"))
      (node (ref "CN1") (pin "14") (pinfunction "P7_14") (pintype "unspecified"))
    )
    (net (code "47") (name "Net-(CN1-P8)") (class "Default")
      (node (ref "C14") (pin "1") (pinfunction "1_1") (pintype "unspecified"))
      (node (ref "CN1") (pin "15") (pinfunction "P8_15") (pintype "unspecified"))
    )
    (net (code "48") (name "Net-(CN1-P9)") (class "Default")
      (node (ref "C13") (pin "1") (pinfunction "1_1") (pintype "unspecified"))
      (node (ref "CN1") (pin "16") (pinfunction "P9_16") (pintype "unspecified"))
    )
    (net (code "49") (name "Net-(CN1-S2)") (class "Default")
      (node (ref "C19") (pin "1") (pinfunction "1_1") (pintype "unspecified"))
      (node (ref "CN1") (pin "2") (pinfunction "S2_2") (pintype "unspecified"))
    )
    (net (code "50") (name "Net-(CN1-S3)") (class "Default")
      (node (ref "C18") (pin "1") (pinfunction "1_1") (pintype "unspecified"))
      (node (ref "CN1") (pin "3") (pinfunction "S3_3") (pintype "unspecified"))
    )
    (net (code "51") (name "Net-(CN1-S5)") (class "Default")
      (node (ref "C17") (pin "1") (pinfunction "1_1") (pintype "unspecified"))
      (node (ref "CN1") (pin "5") (pinfunction "S5_5") (pintype "unspecified"))
    )
    (net (code "52") (name "Net-(CN1-S6)") (class "Default")
      (node (ref "C16") (pin "1") (pinfunction "1_1") (pintype "unspecified"))
      (node (ref "CN1") (pin "6") (pinfunction "S6_6") (pintype "unspecified"))
    )
    (net (code "53") (name "Net-(CN2-P7)") (class "Default")
      (node (ref "C24") (pin "1") (pinfunction "1_1") (pintype "unspecified"))
      (node (ref "CN2") (pin "14") (pinfunction "P7_14") (pintype "unspecified"))
    )
    (net (code "54") (name "Net-(CN2-P8)") (class "Default")
      (node (ref "C25") (pin "1") (pinfunction "1_1") (pintype "unspecified"))
      (node (ref "CN2") (pin "15") (pinfunction "P8_15") (pintype "unspecified"))
    )
    (net (code "55") (name "Net-(CN2-P9)") (class "Default")
      (node (ref "C26") (pin "1") (pinfunction "1_1") (pintype "unspecified"))
      (node (ref "CN2") (pin "16") (pinfunction "P9_16") (pintype "unspecified"))
    )
    (net (code "56") (name "Net-(CN2-S2)") (class "Default")
      (node (ref "C23") (pin "1") (pinfunction "1_1") (pintype "unspecified"))
      (node (ref "CN2") (pin "2") (pinfunction "S2_2") (pintype "unspecified"))
    )
    (net (code "57") (name "Net-(CN2-S3)") (class "Default")
      (node (ref "C22") (pin "1") (pinfunction "1_1") (pintype "unspecified"))
      (node (ref "CN2") (pin "3") (pinfunction "S3_3") (pintype "unspecified"))
    )
    (net (code "58") (name "Net-(CN2-S5)") (class "Default")
      (node (ref "C21") (pin "1") (pinfunction "1_1") (pintype "unspecified"))
      (node (ref "CN2") (pin "5") (pinfunction "S5_5") (pintype "unspecified"))
    )
    (net (code "59") (name "Net-(CN2-S6)") (class "Default")
      (node (ref "C20") (pin "1") (pinfunction "1_1") (pintype "unspecified"))
      (node (ref "CN2") (pin "6") (pinfunction "S6_6") (pintype "unspecified"))
    )
    (net (code "60") (name "Net-(U1-BST)") (class "Default")
      (node (ref "C2") (pin "1") (pinfunction "1_1") (pintype "unspecified"))
      (node (ref "U1") (pin "1") (pinfunction "BST_1") (pintype "unspecified"))
    )
    (net (code "61") (name "Net-(U1-COMP)") (class "Default")
      (node (ref "R2") (pin "1") (pinfunction "1_1") (pintype "unspecified"))
      (node (ref "U1") (pin "6") (pinfunction "COMP_6") (pintype "unspecified"))
    )
    (net (code "62") (name "Net-(U1-EN)") (class "Default")
      (node (ref "R1") (pin "2") (pinfunction "2_2") (pintype "unspecified"))
      (node (ref "U1") (pin "3") (pinfunction "EN_3") (pintype "unspecified"))
    )
    (net (code "63") (name "Net-(U1-FB)") (class "Default")
      (node (ref "R3") (pin "2") (pinfunction "2_2") (pintype "unspecified"))
      (node (ref "R4") (pin "2") (pinfunction "2_2") (pintype "unspecified"))
      (node (ref "U1") (pin "5") (pinfunction "FB_5") (pintype "unspecified"))
    )
    (net (code "64") (name "Net-(U1-RT{slash}CLK)") (class "Default")
      (node (ref "R6") (pin "2") (pinfunction "2_2") (pintype "unspecified"))
      (node (ref "U1") (pin "4") (pinfunction "RT/CLK_4") (pintype "unspecified"))
    )
    (net (code "65") (name "Net-(U1-SW)") (class "Default")
      (node (ref "C2") (pin "2") (pinfunction "2_2") (pintype "unspecified"))
      (node (ref "U1") (pin "8") (pinfunction "SW_8") (pintype "unspecified"))
      (node (ref "U2") (pin "1") (pinfunction "1_1") (pintype "unspecified"))
    )
    (net (code "66") (name "Net-(U5-BST)") (class "Default")
      (node (ref "C7") (pin "1") (pinfunction "1_1") (pintype "unspecified"))
      (node (ref "U5") (pin "1") (pinfunction "BST_1") (pintype "unspecified"))
    )
    (net (code "67") (name "Net-(U5-COMP)") (class "Default")
      (node (ref "R5") (pin "1") (pinfunction "1_1") (pintype "input"))
      (node (ref "U5") (pin "6") (pinfunction "COMP_6") (pintype "unspecified"))
    )
    (net (code "68") (name "Net-(U5-EN)") (class "Default")
      (node (ref "R11") (pin "2") (pinfunction "2_2") (pintype "unspecified"))
      (node (ref "U5") (pin "3") (pinfunction "EN_3") (pintype "unspecified"))
    )
    (net (code "69") (name "Net-(U5-FB)") (class "Default")
      (node (ref "R8") (pin "2") (pinfunction "2_2") (pintype "unspecified"))
      (node (ref "U3") (pin "1") (pinfunction "1_1") (pintype "unspecified"))
      (node (ref "U5") (pin "5") (pinfunction "FB_5") (pintype "unspecified"))
    )
    (net (code "70") (name "Net-(U5-RT{slash}CLK)") (class "Default")
      (node (ref "R7") (pin "2") (pinfunction "2_2") (pintype "unspecified"))
      (node (ref "U5") (pin "4") (pinfunction "RT/CLK_4") (pintype "unspecified"))
    )
    (net (code "71") (name "Net-(U5-SW)") (class "Default")
      (node (ref "C7") (pin "2") (pinfunction "2_2") (pintype "unspecified"))
      (node (ref "U4") (pin "1") (pinfunction "1_1") (pintype "unspecified"))
      (node (ref "U5") (pin "8") (pinfunction "SW_8") (pintype "unspecified"))
    )
    (net (code "72") (name "SATA0_RX_N") (class "Default")
      (node (ref "C17") (pin "2") (pinfunction "2_2") (pintype "unspecified"))
    )
    (net (code "73") (name "SATA0_RX_P") (class "Default")
      (node (ref "C16") (pin "2") (pinfunction "2_2") (pintype "unspecified"))
    )
    (net (code "74") (name "SATA0_TX_N") (class "Default")
      (node (ref "C18") (pin "2") (pinfunction "2_2") (pintype "unspecified"))
    )
    (net (code "75") (name "SATA0_TX_P") (class "Default")
      (node (ref "C19") (pin "2") (pinfunction "2_2") (pintype "unspecified"))
    )
    (net (code "76") (name "SATA1_RX_N") (class "Default")
      (node (ref "C21") (pin "2") (pinfunction "2_2") (pintype "unspecified"))
    )
    (net (code "77") (name "SATA1_RX_P") (class "Default")
      (node (ref "C20") (pin "2") (pinfunction "2_2") (pintype "unspecified"))
    )
    (net (code "78") (name "SATA1_TX_N") (class "Default")
      (node (ref "C22") (pin "2") (pinfunction "2_2") (pintype "unspecified"))
    )
    (net (code "79") (name "SATA1_TX_P") (class "Default")
      (node (ref "C23") (pin "2") (pinfunction "2_2") (pintype "unspecified"))
    )
    (net (code "80") (name "WIFI_CLKREQ_N") (class "Default")
      (node (ref "R12") (pin "2") (pinfunction "2_2") (pintype "unspecified"))
      (node (ref "U6") (pin "53") (pinfunction "53_53") (pintype "unspecified"))
    )
    (net (code "81") (name "WIFI_CLK_N") (class "Default")
      (node (ref "U6") (pin "49") (pinfunction "49_49") (pintype "unspecified"))
    )
    (net (code "82") (name "WIFI_CLK_P") (class "Default")
      (node (ref "U6") (pin "47") (pinfunction "47_47") (pintype "unspecified"))
    )
    (net (code "83") (name "WIFI_RST_N") (class "Default")
      (node (ref "C35") (pin "2") (pinfunction "2_2") (pintype "unspecified"))
      (node (ref "R9") (pin "1") (pinfunction "1_1") (pintype "unspecified"))
      (node (ref "U6") (pin "52") (pinfunction "52_52") (pintype "unspecified"))
    )
    (net (code "84") (name "WIFI_RX_N") (class "Default")
      (node (ref "U6") (pin "37") (pinfunction "37_37") (pintype "unspecified"))
    )
    (net (code "85") (name "WIFI_RX_P") (class "Default")
      (node (ref "U6") (pin "35") (pinfunction "35_35") (pintype "unspecified"))
    )
    (net (code "86") (name "WIFI_TX_N") (class "Default")
      (node (ref "C34") (pin "2") (pinfunction "2_2") (pintype "unspecified"))
    )
    (net (code "87") (name "WIFI_TX_P") (class "Default")
      (node (ref "C33") (pin "2") (pinfunction "2_2") (pintype "unspecified"))
    )
    (net (code "88") (name "WIFI_WAKE_N") (class "Default")
      (node (ref "R13") (pin "2") (pinfunction "2_2") (pintype "unspecified"))
      (node (ref "U6") (pin "55") (pinfunction "55_55") (pintype "unspecified"))
    )
    (net (code "89") (name "unconnected-(CN1-P1-Pad8)") (class "Default")
      (node (ref "CN1") (pin "8") (pinfunction "P1_8") (pintype "unspecified+no_connect"))
    )
    (net (code "90") (name "unconnected-(CN1-P2-Pad9)") (class "Default")
      (node (ref "CN1") (pin "9") (pinfunction "P2_9") (pintype "unspecified+no_connect"))
    )
    (net (code "91") (name "unconnected-(CN1-P3-Pad10)") (class "Default")
      (node (ref "CN1") (pin "10") (pinfunction "P3_10") (pintype "unspecified+no_connect"))
    )
    (net (code "92") (name "unconnected-(CN1-P5-Pad22)") (class "Default")
      (node (ref "CN1") (pin "22") (pinfunction "P5_22") (pintype "unspecified+no_connect"))
    )
    (net (code "93") (name "unconnected-(CN1-P13-Pad20)") (class "Default")
      (node (ref "CN1") (pin "20") (pinfunction "P13_20") (pintype "unspecified+no_connect"))
    )
    (net (code "94") (name "unconnected-(CN1-P14-Pad21)") (class "Default")
      (node (ref "CN1") (pin "21") (pinfunction "P14_21") (pintype "unspecified+no_connect"))
    )
    (net (code "95") (name "unconnected-(CN2-P1-Pad8)") (class "Default")
      (node (ref "CN2") (pin "8") (pinfunction "P1_8") (pintype "unspecified+no_connect"))
    )
    (net (code "96") (name "unconnected-(CN2-P2-Pad9)") (class "Default")
      (node (ref "CN2") (pin "9") (pinfunction "P2_9") (pintype "unspecified+no_connect"))
    )
    (net (code "97") (name "unconnected-(CN2-P3-Pad10)") (class "Default")
      (node (ref "CN2") (pin "10") (pinfunction "P3_10") (pintype "unspecified+no_connect"))
    )
    (net (code "98") (name "unconnected-(CN2-P5-Pad22)") (class "Default")
      (node (ref "CN2") (pin "22") (pinfunction "P5_22") (pintype "unspecified+no_connect"))
    )
    (net (code "99") (name "unconnected-(CN2-P13-Pad20)") (class "Default")
      (node (ref "CN2") (pin "20") (pinfunction "P13_20") (pintype "unspecified+no_connect"))
    )
    (net (code "100") (name "unconnected-(CN2-P14-Pad21)") (class "Default")
      (node (ref "CN2") (pin "21") (pinfunction "P14_21") (pintype "unspecified+no_connect"))
    )
    (net (code "101") (name "unconnected-(U6-Pad6)") (class "Default")
      (node (ref "U6") (pin "6") (pinfunction "6_6") (pintype "unspecified"))
    )
    (net (code "102") (name "unconnected-(U6-Pad8)") (class "Default")
      (node (ref "U6") (pin "8") (pinfunction "8_8") (pintype "unspecified"))
    )
    (net (code "103") (name "unconnected-(U6-Pad9)") (class "Default")
      (node (ref "U6") (pin "9") (pinfunction "9_9") (pintype "unspecified"))
    )
    (net (code "104") (name "unconnected-(U6-Pad10)") (class "Default")
      (node (ref "U6") (pin "10") (pinfunction "10_10") (pintype "unspecified"))
    )
    (net (code "105") (name "unconnected-(U6-Pad11)") (class "Default")
      (node (ref "U6") (pin "11") (pinfunction "11_11") (pintype "unspecified"))
    )
    (net (code "106") (name "unconnected-(U6-Pad12)") (class "Default")
      (node (ref "U6") (pin "12") (pinfunction "12_12") (pintype "unspecified"))
    )
    (net (code "107") (name "unconnected-(U6-Pad13)") (class "Default")
      (node (ref "U6") (pin "13") (pinfunction "13_13") (pintype "unspecified"))
    )
    (net (code "108") (name "unconnected-(U6-Pad14)") (class "Default")
      (node (ref "U6") (pin "14") (pinfunction "14_14") (pintype "unspecified"))
    )
    (net (code "109") (name "unconnected-(U6-Pad15)") (class "Default")
      (node (ref "U6") (pin "15") (pinfunction "15_15") (pintype "unspecified"))
    )
    (net (code "110") (name "unconnected-(U6-Pad16)") (class "Default")
      (node (ref "U6") (pin "16") (pinfunction "16_16") (pintype "unspecified"))
    )
    (net (code "111") (name "unconnected-(U6-Pad17)") (class "Default")
      (node (ref "U6") (pin "17") (pinfunction "17_17") (pintype "unspecified"))
    )
    (net (code "112") (name "unconnected-(U6-Pad18)") (class "Default")
      (node (ref "U6") (pin "18") (pinfunction "18_18") (pintype "unspecified"))
    )
    (net (code "113") (name "unconnected-(U6-Pad19)") (class "Default")
      (node (ref "U6") (pin "19") (pinfunction "19_19") (pintype "unspecified"))
    )
    (net (code "114") (name "unconnected-(U6-Pad20)") (class "Default")
      (node (ref "U6") (pin "20") (pinfunction "20_20") (pintype "unspecified"))
    )
    (net (code "115") (name "unconnected-(U6-Pad21)") (class "Default")
      (node (ref "U6") (pin "21") (pinfunction "21_21") (pintype "unspecified"))
    )
    (net (code "116") (name "unconnected-(U6-Pad22)") (class "Default")
      (node (ref "U6") (pin "22") (pinfunction "22_22") (pintype "unspecified"))
    )
    (net (code "117") (name "unconnected-(U6-Pad23)") (class "Default")
      (node (ref "U6") (pin "23") (pinfunction "23_23") (pintype "unspecified"))
    )
    (net (code "118") (name "unconnected-(U6-Pad32)") (class "Default")
      (node (ref "U6") (pin "32") (pinfunction "32_32") (pintype "unspecified"))
    )
    (net (code "119") (name "unconnected-(U6-Pad34)") (class "Default")
      (node (ref "U6") (pin "34") (pinfunction "34_34") (pintype "unspecified"))
    )
    (net (code "120") (name "unconnected-(U6-Pad36)") (class "Default")
      (node (ref "U6") (pin "36") (pinfunction "36_36") (pintype "unspecified"))
    )
    (net (code "121") (name "unconnected-(U6-Pad38)") (class "Default")
      (node (ref "U6") (pin "38") (pinfunction "38_38") (pintype "unspecified"))
    )
    (net (code "122") (name "unconnected-(U6-Pad40)") (class "Default")
      (node (ref "U6") (pin "40") (pinfunction "40_40") (pintype "unspecified"))
    )
    (net (code "123") (name "unconnected-(U6-Pad42)") (class "Default")
      (node (ref "U6") (pin "42") (pinfunction "42_42") (pintype "unspecified"))
    )
    (net (code "124") (name "unconnected-(U6-Pad44)") (class "Default")
      (node (ref "U6") (pin "44") (pinfunction "44_44") (pintype "unspecified"))
    )
    (net (code "125") (name "unconnected-(U6-Pad46)") (class "Default")
      (node (ref "U6") (pin "46") (pinfunction "46_46") (pintype "unspecified"))
    )
    (net (code "126") (name "unconnected-(U6-Pad48)") (class "Default")
      (node (ref "U6") (pin "48") (pinfunction "48_48") (pintype "unspecified"))
    )
    (net (code "127") (name "unconnected-(U6-Pad50)") (class "Default")
      (node (ref "U6") (pin "50") (pinfunction "50_50") (pintype "unspecified"))
    )
    (net (code "128") (name "unconnected-(U6-Pad54)") (class "Default")
      (node (ref "U6") (pin "54") (pinfunction "54_54") (pintype "unspecified"))
    )
    (net (code "129") (name "unconnected-(U6-Pad56)") (class "Default")
      (node (ref "U6") (pin "56") (pinfunction "56_56") (pintype "unspecified"))
    )
    (net (code "130") (name "unconnected-(U6-Pad58)") (class "Default")
      (node (ref "U6") (pin "58") (pinfunction "58_58") (pintype "unspecified"))
    )
    (net (code "131") (name "unconnected-(U6-Pad59)") (class "Default")
      (node (ref "U6") (pin "59") (pinfunction "59_59") (pintype "unspecified"))
    )
    (net (code "132") (name "unconnected-(U6-Pad60)") (class "Default")
      (node (ref "U6") (pin "60") (pinfunction "60_60") (pintype "unspecified"))
    )
    (net (code "133") (name "unconnected-(U6-Pad61)") (class "Default")
      (node (ref "U6") (pin "61") (pinfunction "61_61") (pintype "unspecified"))
    )
    (net (code "134") (name "unconnected-(U6-Pad62)") (class "Default")
      (node (ref "U6") (pin "62") (pinfunction "62_62") (pintype "unspecified"))
    )
    (net (code "135") (name "unconnected-(U6-Pad64)") (class "Default")
      (node (ref "U6") (pin "64") (pinfunction "64_64") (pintype "unspecified"))
    )
    (net (code "136") (name "unconnected-(U6-Pad65)") (class "Default")
      (node (ref "U6") (pin "65") (pinfunction "65_65") (pintype "unspecified"))
    )
    (net (code "137") (name "unconnected-(U6-Pad66)") (class "Default")
      (node (ref "U6") (pin "66") (pinfunction "66_66") (pintype "unspecified"))
    )
    (net (code "138") (name "unconnected-(U6-Pad67)") (class "Default")
      (node (ref "U6") (pin "67") (pinfunction "67_67") (pintype "unspecified"))
    )
    (net (code "139") (name "unconnected-(U6-Pad68)") (class "Default")
      (node (ref "U6") (pin "68") (pinfunction "68_68") (pintype "unspecified"))
    )
    (net (code "140") (name "unconnected-(U6-Pad70)") (class "Default")
      (node (ref "U6") (pin "70") (pinfunction "70_70") (pintype "unspecified"))
    )
    (net (code "141") (name "unconnected-(U6-Pad71)") (class "Default")
      (node (ref "U6") (pin "71") (pinfunction "71_71") (pintype "unspecified"))
    )
    (net (code "142") (name "unconnected-(U6-Pad73)") (class "Default")
      (node (ref "U6") (pin "73") (pinfunction "73_73") (pintype "unspecified"))
    )
    (net (code "143") (name "unconnected-(U7-Pad6)") (class "Default")
      (node (ref "U7") (pin "6") (pinfunction "6_6") (pintype "unspecified"))
    )
    (net (code "144") (name "unconnected-(U7-Pad8)") (class "Default")
      (node (ref "U7") (pin "8") (pinfunction "8_8") (pintype "unspecified"))
    )
    (net (code "145") (name "unconnected-(U7-Pad10)") (class "Default")
      (node (ref "U7") (pin "10") (pinfunction "10_10") (pintype "unspecified"))
    )
    (net (code "146") (name "unconnected-(U7-Pad12)") (class "Default")
      (node (ref "U7") (pin "12") (pinfunction "12_12") (pintype "unspecified"))
    )
    (net (code "147") (name "unconnected-(U7-Pad14)") (class "Default")
      (node (ref "U7") (pin "14") (pinfunction "14_14") (pintype "unspecified"))
    )
    (net (code "148") (name "unconnected-(U7-Pad16)") (class "Default")
      (node (ref "U7") (pin "16") (pinfunction "16_16") (pintype "unspecified"))
    )
    (net (code "149") (name "unconnected-(U7-Pad18)") (class "Default")
      (node (ref "U7") (pin "18") (pinfunction "18_18") (pintype "unspecified"))
    )
    (net (code "150") (name "unconnected-(U7-Pad20)") (class "Default")
      (node (ref "U7") (pin "20") (pinfunction "20_20") (pintype "unspecified"))
    )
    (net (code "151") (name "unconnected-(U7-Pad22)") (class "Default")
      (node (ref "U7") (pin "22") (pinfunction "22_22") (pintype "unspecified"))
    )
    (net (code "152") (name "unconnected-(U7-Pad24)") (class "Default")
      (node (ref "U7") (pin "24") (pinfunction "24_24") (pintype "unspecified"))
    )
    (net (code "153") (name "unconnected-(U7-Pad26)") (class "Default")
      (node (ref "U7") (pin "26") (pinfunction "26_26") (pintype "unspecified"))
    )
    (net (code "154") (name "unconnected-(U7-Pad28)") (class "Default")
      (node (ref "U7") (pin "28") (pinfunction "28_28") (pintype "unspecified"))
    )
    (net (code "155") (name "unconnected-(U7-Pad30)") (class "Default")
      (node (ref "U7") (pin "30") (pinfunction "30_30") (pintype "unspecified"))
    )
    (net (code "156") (name "unconnected-(U7-Pad32)") (class "Default")
      (node (ref "U7") (pin "32") (pinfunction "32_32") (pintype "unspecified"))
    )
    (net (code "157") (name "unconnected-(U7-Pad34)") (class "Default")
      (node (ref "U7") (pin "34") (pinfunction "34_34") (pintype "unspecified"))
    )
    (net (code "158") (name "unconnected-(U7-Pad36)") (class "Default")
      (node (ref "U7") (pin "36") (pinfunction "36_36") (pintype "unspecified"))
    )
    (net (code "159") (name "unconnected-(U7-Pad38)") (class "Default")
      (node (ref "U7") (pin "38") (pinfunction "38_38") (pintype "unspecified"))
    )
    (net (code "160") (name "unconnected-(U7-Pad40)") (class "Default")
      (node (ref "U7") (pin "40") (pinfunction "40_40") (pintype "unspecified"))
    )
    (net (code "161") (name "unconnected-(U7-Pad42)") (class "Default")
      (node (ref "U7") (pin "42") (pinfunction "42_42") (pintype "unspecified"))
    )
    (net (code "162") (name "unconnected-(U7-Pad44)") (class "Default")
      (node (ref "U7") (pin "44") (pinfunction "44_44") (pintype "unspecified"))
    )
    (net (code "163") (name "unconnected-(U7-Pad46)") (class "Default")
      (node (ref "U7") (pin "46") (pinfunction "46_46") (pintype "unspecified"))
    )
    (net (code "164") (name "unconnected-(U7-Pad48)") (class "Default")
      (node (ref "U7") (pin "48") (pinfunction "48_48") (pintype "unspecified"))
    )
    (net (code "165") (name "unconnected-(U7-Pad56)") (class "Default")
      (node (ref "U7") (pin "56") (pinfunction "56_56") (pintype "unspecified"))
    )
    (net (code "166") (name "unconnected-(U7-Pad58)") (class "Default")
      (node (ref "U7") (pin "58") (pinfunction "58_58") (pintype "unspecified"))
    )
    (net (code "167") (name "unconnected-(U7-Pad67)") (class "Default")
      (node (ref "U7") (pin "67") (pinfunction "67_67") (pintype "unspecified"))
    )
    (net (code "168") (name "unconnected-(U7-Pad68)") (class "Default")
      (node (ref "U7") (pin "68") (pinfunction "68_68") (pintype "unspecified"))
    )
    (net (code "169") (name "unconnected-(U7-Pad69)") (class "Default")
      (node (ref "U7") (pin "69") (pinfunction "69_69") (pintype "unspecified"))
    )
  )
)
